# display.net
KiCad netlist of a schematic drawn in EAGLE
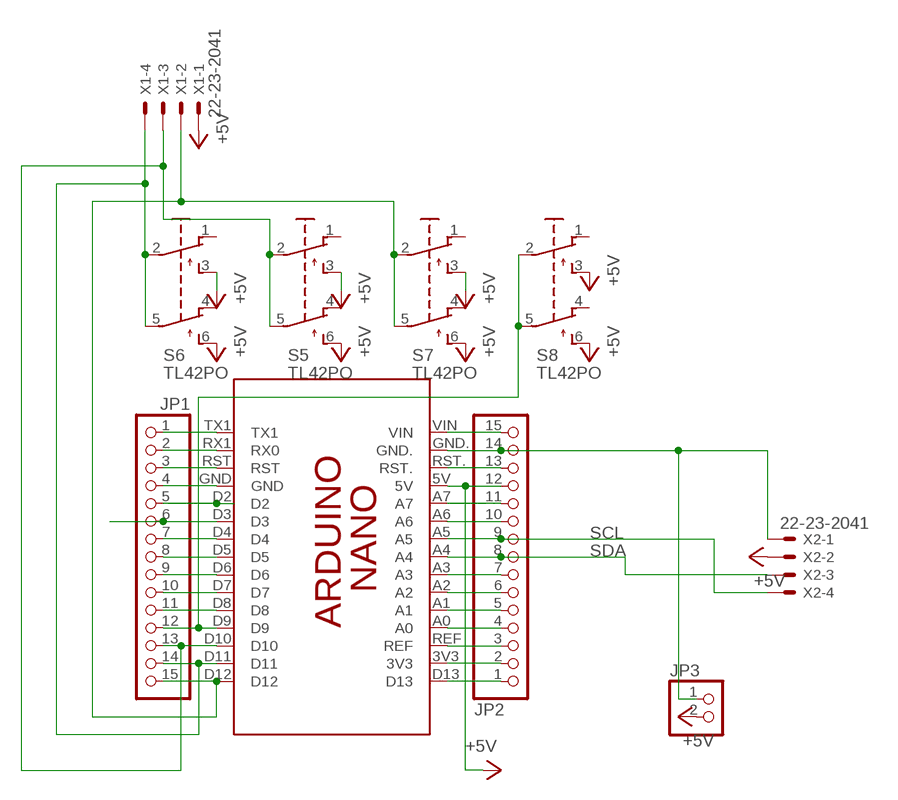
[diagram p0: schematic, sheet 1]

(export (version "E")
  (design (tool "Eeschema 10.0.6"))
  (components
    (comp (ref "JP1")
      (value "PINHD-1X15")
      (footprint "eagle-import:1X15")
      (libsource (lib "eagle-import") (part "PINHD-1X15"))
    )
    (comp (ref "JP2")
      (value "PINHD-1X15")
      (footprint "eagle-import:1X15")
      (libsource (lib "eagle-import") (part "PINHD-1X15"))
    )
    (comp (ref "JP3")
      (value "PINHD-1X2")
      (footprint "eagle-import:1X02")
      (libsource (lib "eagle-import") (part "PINHD-1X2"))
    )
    (comp (ref "PCB1")
      (value "ARDUINO_NANO")
      (footprint "eagle-import:ARDUINO_NANO")
      (libsource (lib "eagle-import") (part "ARDUINO_NANO"))
    )
    (comp (ref "S5")
      (value "TL42PO")
      (footprint "eagle-import:TL4XPO")
      (libsource (lib "eagle-import") (part "TL42PO"))
    )
    (comp (ref "S6")
      (value "TL42PO")
      (footprint "eagle-import:TL4XPO")
      (libsource (lib "eagle-import") (part "TL42PO"))
    )
    (comp (ref "S7")
      (value "TL42PO")
      (footprint "eagle-import:TL4XPO")
      (libsource (lib "eagle-import") (part "TL42PO"))
    )
    (comp (ref "S8")
      (value "TL42PO")
      (footprint "eagle-import:TL4XPO")
      (libsource (lib "eagle-import") (part "TL42PO"))
    )
    (comp (ref "X1")
      (value "22-23-2041")
      (footprint "eagle-import:22-23-2041")
      (fields (field (name "MF") "MOLEX"))
      (libsource (lib "eagle-import") (part "22-23-2041"))
    )
    (comp (ref "X2")
      (value "22-23-2041")
      (footprint "eagle-import:22-23-2041")
      (fields (field (name "MF") "MOLEX"))
      (libsource (lib "eagle-import") (part "22-23-2041"))
    )
  )
  (nets
    (net (code "1") (name "+5V") (class "Default")
      (node (ref "JP2") (pin "12") (pinfunction "12_12") (pintype "passive"))
      (node (ref "JP3") (pin "2") (pinfunction "2_2") (pintype "passive"))
      (node (ref "PCB1") (pin "5V") (pinfunction "5V_5V") (pintype "bidirectional"))
      (node (ref "S5") (pin "3") (pinfunction "S_3") (pintype "passive"))
      (node (ref "S5") (pin "6") (pinfunction "S1_6") (pintype "passive"))
      (node (ref "S6") (pin "3") (pinfunction "S_3") (pintype "passive"))
      (node (ref "S6") (pin "6") (pinfunction "S1_6") (pintype "passive"))
      (node (ref "S7") (pin "3") (pinfunction "S_3") (pintype "passive"))
      (node (ref "S7") (pin "6") (pinfunction "S1_6") (pintype "passive"))
      (node (ref "S8") (pin "3") (pinfunction "S_3") (pintype "passive"))
      (node (ref "S8") (pin "6") (pinfunction "S1_6") (pintype "passive"))
      (node (ref "X1") (pin "1") (pinfunction "S_1") (pintype "passive"))
      (node (ref "X2") (pin "2") (pinfunction "S_2") (pintype "passive"))
    )
    (net (code "2") (name "/SCL") (class "Default")
      (node (ref "JP2") (pin "9") (pinfunction "9_9") (pintype "passive"))
      (node (ref "PCB1") (pin "A5") (pinfunction "A5_A5") (pintype "bidirectional"))
      (node (ref "X2") (pin "4") (pinfunction "S_4") (pintype "passive"))
    )
    (net (code "3") (name "/SDA") (class "Default")
      (node (ref "JP2") (pin "8") (pinfunction "8_8") (pintype "passive"))
      (node (ref "PCB1") (pin "A4") (pinfunction "A4_A4") (pintype "bidirectional"))
      (node (ref "X2") (pin "3") (pinfunction "S_3") (pintype "passive"))
    )
    (net (code "4") (name "Net-(JP1-Pad1)") (class "Default")
      (node (ref "JP1") (pin "1") (pinfunction "1_1") (pintype "passive"))
      (node (ref "PCB1") (pin "TX1") (pinfunction "TX1_TX1") (pintype "bidirectional"))
    )
    (net (code "5") (name "Net-(JP1-Pad3)") (class "Default")
      (node (ref "JP1") (pin "3") (pinfunction "3_3") (pintype "passive"))
      (node (ref "PCB1") (pin "RST") (pinfunction "RST_RST") (pintype "bidirectional"))
    )
    (net (code "6") (name "Net-(JP1-Pad4)") (class "Default")
      (node (ref "JP1") (pin "4") (pinfunction "4_4") (pintype "passive"))
      (node (ref "PCB1") (pin "GND") (pinfunction "GND_GND") (pintype "bidirectional"))
    )
    (net (code "7") (name "Net-(JP1-Pad5)") (class "Default")
      (node (ref "JP1") (pin "5") (pinfunction "5_5") (pintype "passive"))
      (node (ref "PCB1") (pin "D2") (pinfunction "D2_D2") (pintype "bidirectional"))
    )
    (net (code "8") (name "Net-(JP1-Pad6)") (class "Default")
      (node (ref "JP1") (pin "6") (pinfunction "6_6") (pintype "passive"))
      (node (ref "PCB1") (pin "D3") (pinfunction "D3_D3") (pintype "bidirectional"))
    )
    (net (code "9") (name "Net-(JP1-Pad7)") (class "Default")
      (node (ref "JP1") (pin "7") (pinfunction "7_7") (pintype "passive"))
      (node (ref "PCB1") (pin "D4") (pinfunction "D4_D4") (pintype "bidirectional"))
    )
    (net (code "10") (name "Net-(JP1-Pad8)") (class "Default")
      (node (ref "JP1") (pin "8") (pinfunction "8_8") (pintype "passive"))
      (node (ref "PCB1") (pin "D5") (pinfunction "D5_D5") (pintype "bidirectional"))
    )
    (net (code "11") (name "Net-(JP1-Pad9)") (class "Default")
      (node (ref "JP1") (pin "9") (pinfunction "9_9") (pintype "passive"))
      (node (ref "PCB1") (pin "D6") (pinfunction "D6_D6") (pintype "bidirectional"))
    )
    (net (code "12") (name "Net-(JP1-Pad10)") (class "Default")
      (node (ref "JP1") (pin "10") (pinfunction "10_10") (pintype "passive"))
      (node (ref "PCB1") (pin "D7") (pinfunction "D7_D7") (pintype "bidirectional"))
    )
    (net (code "13") (name "Net-(JP1-Pad11)") (class "Default")
      (node (ref "JP1") (pin "11") (pinfunction "11_11") (pintype "passive"))
      (node (ref "PCB1") (pin "D8") (pinfunction "D8_D8") (pintype "bidirectional"))
    )
    (net (code "14") (name "Net-(JP2-Pad1)") (class "Default")
      (node (ref "JP2") (pin "1") (pinfunction "1_1") (pintype "passive"))
      (node (ref "PCB1") (pin "D13") (pinfunction "D13_D13") (pintype "bidirectional"))
    )
    (net (code "15") (name "Net-(JP2-Pad2)") (class "Default")
      (node (ref "JP2") (pin "2") (pinfunction "2_2") (pintype "passive"))
      (node (ref "PCB1") (pin "3V3") (pinfunction "3V3_3V3") (pintype "bidirectional"))
    )
    (net (code "16") (name "Net-(JP2-Pad3)") (class "Default")
      (node (ref "JP2") (pin "3") (pinfunction "3_3") (pintype "passive"))
      (node (ref "PCB1") (pin "REF") (pinfunction "REF_REF") (pintype "bidirectional"))
    )
    (net (code "17") (name "Net-(JP2-Pad4)") (class "Default")
      (node (ref "JP2") (pin "4") (pinfunction "4_4") (pintype "passive"))
      (node (ref "PCB1") (pin "A0") (pinfunction "A0_A0") (pintype "bidirectional"))
    )
    (net (code "18") (name "Net-(JP2-Pad5)") (class "Default")
      (node (ref "JP2") (pin "5") (pinfunction "5_5") (pintype "passive"))
      (node (ref "PCB1") (pin "A1") (pinfunction "A1_A1") (pintype "bidirectional"))
    )
    (net (code "19") (name "Net-(JP2-Pad6)") (class "Default")
      (node (ref "JP2") (pin "6") (pinfunction "6_6") (pintype "passive"))
      (node (ref "PCB1") (pin "A2") (pinfunction "A2_A2") (pintype "bidirectional"))
    )
    (net (code "20") (name "Net-(JP2-Pad7)") (class "Default")
      (node (ref "JP2") (pin "7") (pinfunction "7_7") (pintype "passive"))
      (node (ref "PCB1") (pin "A3") (pinfunction "A3_A3") (pintype "bidirectional"))
    )
    (net (code "21") (name "Net-(JP2-Pad10)") (class "Default")
      (node (ref "JP2") (pin "10") (pinfunction "10_10") (pintype "passive"))
      (node (ref "PCB1") (pin "A6") (pinfunction "A6_A6") (pintype "bidirectional"))
    )
    (net (code "22") (name "Net-(JP2-Pad11)") (class "Default")
      (node (ref "JP2") (pin "11") (pinfunction "11_11") (pintype "passive"))
      (node (ref "PCB1") (pin "A7") (pinfunction "A7_A7") (pintype "bidirectional"))
    )
    (net (code "23") (name "Net-(JP2-Pad13)") (class "Default")
      (node (ref "JP2") (pin "13") (pinfunction "13_13") (pintype "passive"))
      (node (ref "PCB1") (pin "RST.") (pinfunction "RST._RST.") (pintype "bidirectional"))
    )
    (net (code "24") (name "Net-(JP2-Pad15)") (class "Default")
      (node (ref "JP2") (pin "15") (pinfunction "15_15") (pintype "passive"))
      (node (ref "PCB1") (pin "VIN") (pinfunction "VIN_VIN") (pintype "bidirectional"))
    )
    (net (code "25") (name "Net-(PCB1-RX0)") (class "Default")
      (node (ref "JP1") (pin "2") (pinfunction "2_2") (pintype "passive"))
      (node (ref "PCB1") (pin "RX1") (pinfunction "RX0_RX1") (pintype "bidirectional"))
    )
    (net (code "26") (name "Net-(S5-P)") (class "Default")
      (node (ref "JP1") (pin "13") (pinfunction "13_13") (pintype "passive"))
      (node (ref "PCB1") (pin "D10") (pinfunction "D10_D10") (pintype "bidirectional"))
      (node (ref "S5") (pin "2") (pinfunction "P_2") (pintype "passive"))
      (node (ref "S5") (pin "5") (pinfunction "P1_5") (pintype "passive"))
      (node (ref "X1") (pin "3") (pinfunction "S_3") (pintype "passive"))
    )
    (net (code "27") (name "Net-(S6-P)") (class "Default")
      (node (ref "JP1") (pin "14") (pinfunction "14_14") (pintype "passive"))
      (node (ref "PCB1") (pin "D11") (pinfunction "D11_D11") (pintype "bidirectional"))
      (node (ref "S6") (pin "2") (pinfunction "P_2") (pintype "passive"))
      (node (ref "S6") (pin "5") (pinfunction "P1_5") (pintype "passive"))
      (node (ref "X1") (pin "4") (pinfunction "S_4") (pintype "passive"))
    )
    (net (code "28") (name "Net-(S7-P)") (class "Default")
      (node (ref "JP1") (pin "15") (pinfunction "15_15") (pintype "passive"))
      (node (ref "PCB1") (pin "D12") (pinfunction "D12_D12") (pintype "bidirectional"))
      (node (ref "S7") (pin "2") (pinfunction "P_2") (pintype "passive"))
      (node (ref "S7") (pin "5") (pinfunction "P1_5") (pintype "passive"))
      (node (ref "X1") (pin "2") (pinfunction "S_2") (pintype "passive"))
    )
    (net (code "29") (name "Net-(S8-P)") (class "Default")
      (node (ref "JP1") (pin "12") (pinfunction "12_12") (pintype "passive"))
      (node (ref "PCB1") (pin "D9") (pinfunction "D9_D9") (pintype "bidirectional"))
      (node (ref "S8") (pin "2") (pinfunction "P_2") (pintype "passive"))
      (node (ref "S8") (pin "5") (pinfunction "P1_5") (pintype "passive"))
    )
    (net (code "30") (name "Net-(X2A-S)") (class "Default")
      (node (ref "JP2") (pin "14") (pinfunction "14_14") (pintype "passive"))
      (node (ref "JP3") (pin "1") (pinfunction "1_1") (pintype "passive"))
      (node (ref "PCB1") (pin "GND.") (pinfunction "GND._GND.") (pintype "bidirectional"))
      (node (ref "X2") (pin "1") (pinfunction "S_1") (pintype "passive"))
    )
    (net (code "31") (name "unconnected-(S5-O-Pad1)") (class "Default")
      (node (ref "S5") (pin "1") (pinfunction "O_1") (pintype "passive"))
    )
    (net (code "32") (name "unconnected-(S5-O1-Pad4)") (class "Default")
      (node (ref "S5") (pin "4") (pinfunction "O1_4") (pintype "passive"))
    )
    (net (code "33") (name "unconnected-(S6-O-Pad1)") (class "Default")
      (node (ref "S6") (pin "1") (pinfunction "O_1") (pintype "passive"))
    )
    (net (code "34") (name "unconnected-(S6-O1-Pad4)") (class "Default")
      (node (ref "S6") (pin "4") (pinfunction "O1_4") (pintype "passive"))
    )
    (net (code "35") (name "unconnected-(S7-O-Pad1)") (class "Default")
      (node (ref "S7") (pin "1") (pinfunction "O_1") (pintype "passive"))
    )
    (net (code "36") (name "unconnected-(S7-O1-Pad4)") (class "Default")
      (node (ref "S7") (pin "4") (pinfunction "O1_4") (pintype "passive"))
    )
    (net (code "37") (name "unconnected-(S8-O-Pad1)") (class "Default")
      (node (ref "S8") (pin "1") (pinfunction "O_1") (pintype "passive"))
    )
    (net (code "38") (name "unconnected-(S8-O1-Pad4)") (class "Default")
      (node (ref "S8") (pin "4") (pinfunction "O1_4") (pintype "passive"))
    )
  )
)
